# PowerBoard.net
KiCad netlist of a schematic drawn in EAGLE
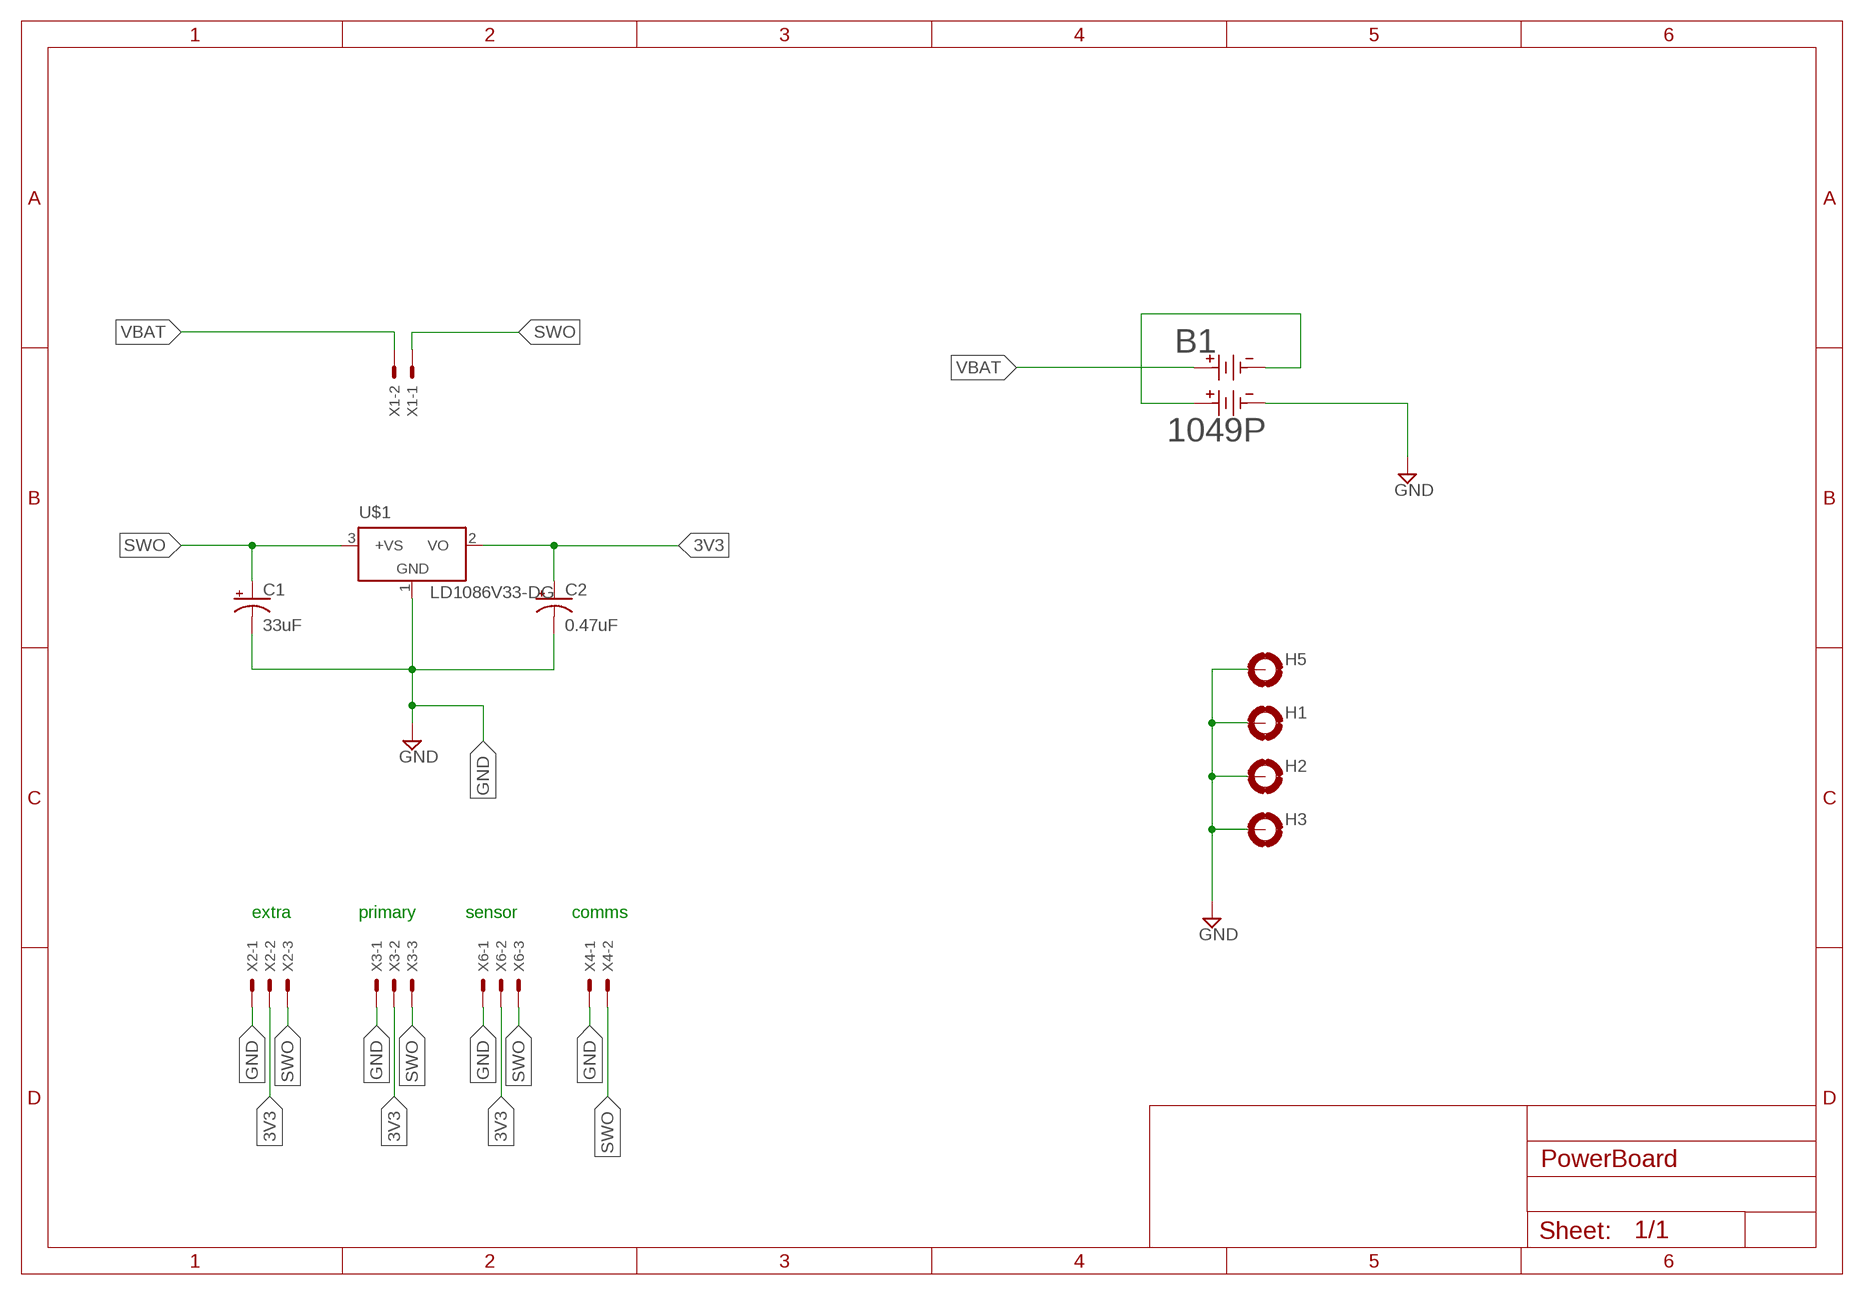
[diagram p0: schematic, sheet 1]

(export (version "E")
  (design (tool "Eeschema 10.0.6"))
  (components
    (comp (ref "B1")
      (value "1049P")
      (footprint "eagle-import:1049P_KEY")
      (fields (field (name "COPYRIGHT") "Copyright (C) 2024 Ultra Librarian. All rights reserved."))
      (libsource (lib "eagle-import") (part "1049P"))
    )
    (comp (ref "C1")
      (value "33uF")
      (footprint "eagle-import:E2,5-5")
      (libsource (lib "eagle-import") (part "CPOL-USE2.5-5"))
    )
    (comp (ref "C2")
      (value "0.47uF")
      (footprint "eagle-import:E2,5-5")
      (libsource (lib "eagle-import") (part "CPOL-USE2.5-5"))
    )
    (comp (ref "H1")
      (value "MOUNT-PAD-ROUND3.0")
      (footprint "eagle-import:3,0-PAD")
      (libsource (lib "eagle-import") (part "MOUNT-PAD-ROUND3.0"))
    )
    (comp (ref "H2")
      (value "MOUNT-PAD-ROUND3.0")
      (footprint "eagle-import:3,0-PAD")
      (libsource (lib "eagle-import") (part "MOUNT-PAD-ROUND3.0"))
    )
    (comp (ref "H3")
      (value "MOUNT-PAD-ROUND3.0")
      (footprint "eagle-import:3,0-PAD")
      (libsource (lib "eagle-import") (part "MOUNT-PAD-ROUND3.0"))
    )
    (comp (ref "H5")
      (value "MOUNT-PAD-ROUND3.0")
      (footprint "eagle-import:3,0-PAD")
      (libsource (lib "eagle-import") (part "MOUNT-PAD-ROUND3.0"))
    )
    (comp (ref "U$1")
      (value "LD1086V33-DG")
      (footprint "eagle-import:TO220H")
      (libsource (lib "eagle-import") (part "LD1086V33-DG"))
    )
    (comp (ref "X1")
      (value "JST-XH-02-PIN")
      (footprint "eagle-import:JST-XH_S2B")
      (libsource (lib "eagle-import") (part "JST-XH-02-PIN"))
    )
    (comp (ref "X2")
      (value "JST-XH-03-PIN")
      (footprint "eagle-import:JST-XH_S3B")
      (libsource (lib "eagle-import") (part "JST-XH-03-PIN"))
    )
    (comp (ref "X3")
      (value "JST-XH-03-PIN")
      (footprint "eagle-import:JST-XH_S3B")
      (libsource (lib "eagle-import") (part "JST-XH-03-PIN"))
    )
    (comp (ref "X4")
      (value "JST-XH-02-PIN")
      (footprint "eagle-import:JST-XH_S2B")
      (libsource (lib "eagle-import") (part "JST-XH-02-PIN"))
    )
    (comp (ref "X6")
      (value "JST-XH-03-PIN")
      (footprint "eagle-import:JST-XH_S3B")
      (libsource (lib "eagle-import") (part "JST-XH-03-PIN"))
    )
  )
  (nets
    (net (code "1") (name "3V3") (class "Default")
      (node (ref "C2") (pin "+") (pinfunction "+_+") (pintype "passive"))
      (node (ref "U$1") (pin "2") (pinfunction "VO_2") (pintype "input"))
      (node (ref "X2") (pin "PIN2") (pinfunction "S_PIN2") (pintype "passive"))
      (node (ref "X3") (pin "PIN2") (pinfunction "S_PIN2") (pintype "passive"))
      (node (ref "X6") (pin "PIN2") (pinfunction "S_PIN2") (pintype "passive"))
    )
    (net (code "2") (name "GND") (class "Default")
      (node (ref "B1") (pin "3") (pinfunction "3_3") (pintype "passive"))
      (node (ref "C1") (pin "-") (pinfunction "-_-") (pintype "passive"))
      (node (ref "C2") (pin "-") (pinfunction "-_-") (pintype "passive"))
      (node (ref "H1") (pin "B3,0") (pinfunction "MOUNT_B3,0") (pintype "passive"))
      (node (ref "H2") (pin "B3,0") (pinfunction "MOUNT_B3,0") (pintype "passive"))
      (node (ref "H3") (pin "B3,0") (pinfunction "MOUNT_B3,0") (pintype "passive"))
      (node (ref "H5") (pin "B3,0") (pinfunction "MOUNT_B3,0") (pintype "passive"))
      (node (ref "U$1") (pin "1") (pinfunction "GND_1") (pintype "power_in"))
      (node (ref "X2") (pin "PIN1") (pinfunction "S_PIN1") (pintype "passive"))
      (node (ref "X3") (pin "PIN1") (pinfunction "S_PIN1") (pintype "passive"))
      (node (ref "X4") (pin "PIN1") (pinfunction "S_PIN1") (pintype "passive"))
      (node (ref "X6") (pin "PIN1") (pinfunction "S_PIN1") (pintype "passive"))
    )
    (net (code "3") (name "Net-(B1-Pad2)") (class "Default")
      (node (ref "B1") (pin "2") (pinfunction "2_2") (pintype "passive"))
      (node (ref "B1") (pin "4") (pinfunction "4_4") (pintype "passive"))
    )
    (net (code "4") (name "SWO") (class "Default")
      (node (ref "C1") (pin "+") (pinfunction "+_+") (pintype "passive"))
      (node (ref "U$1") (pin "3") (pinfunction "+VS_3") (pintype "input"))
      (node (ref "X1") (pin "PIN1") (pinfunction "S_PIN1") (pintype "passive"))
      (node (ref "X2") (pin "PIN3") (pinfunction "S_PIN3") (pintype "passive"))
      (node (ref "X3") (pin "PIN3") (pinfunction "S_PIN3") (pintype "passive"))
      (node (ref "X4") (pin "PIN2") (pinfunction "S_PIN2") (pintype "passive"))
      (node (ref "X6") (pin "PIN3") (pinfunction "S_PIN3") (pintype "passive"))
    )
    (net (code "5") (name "VBAT") (class "Default")
      (node (ref "B1") (pin "1") (pinfunction "1_1") (pintype "passive"))
      (node (ref "X1") (pin "PIN2") (pinfunction "S_PIN2") (pintype "passive"))
    )
  )
)
